# Sheet1.net
KiCad netlist of a schematic drawn in Altium Designer
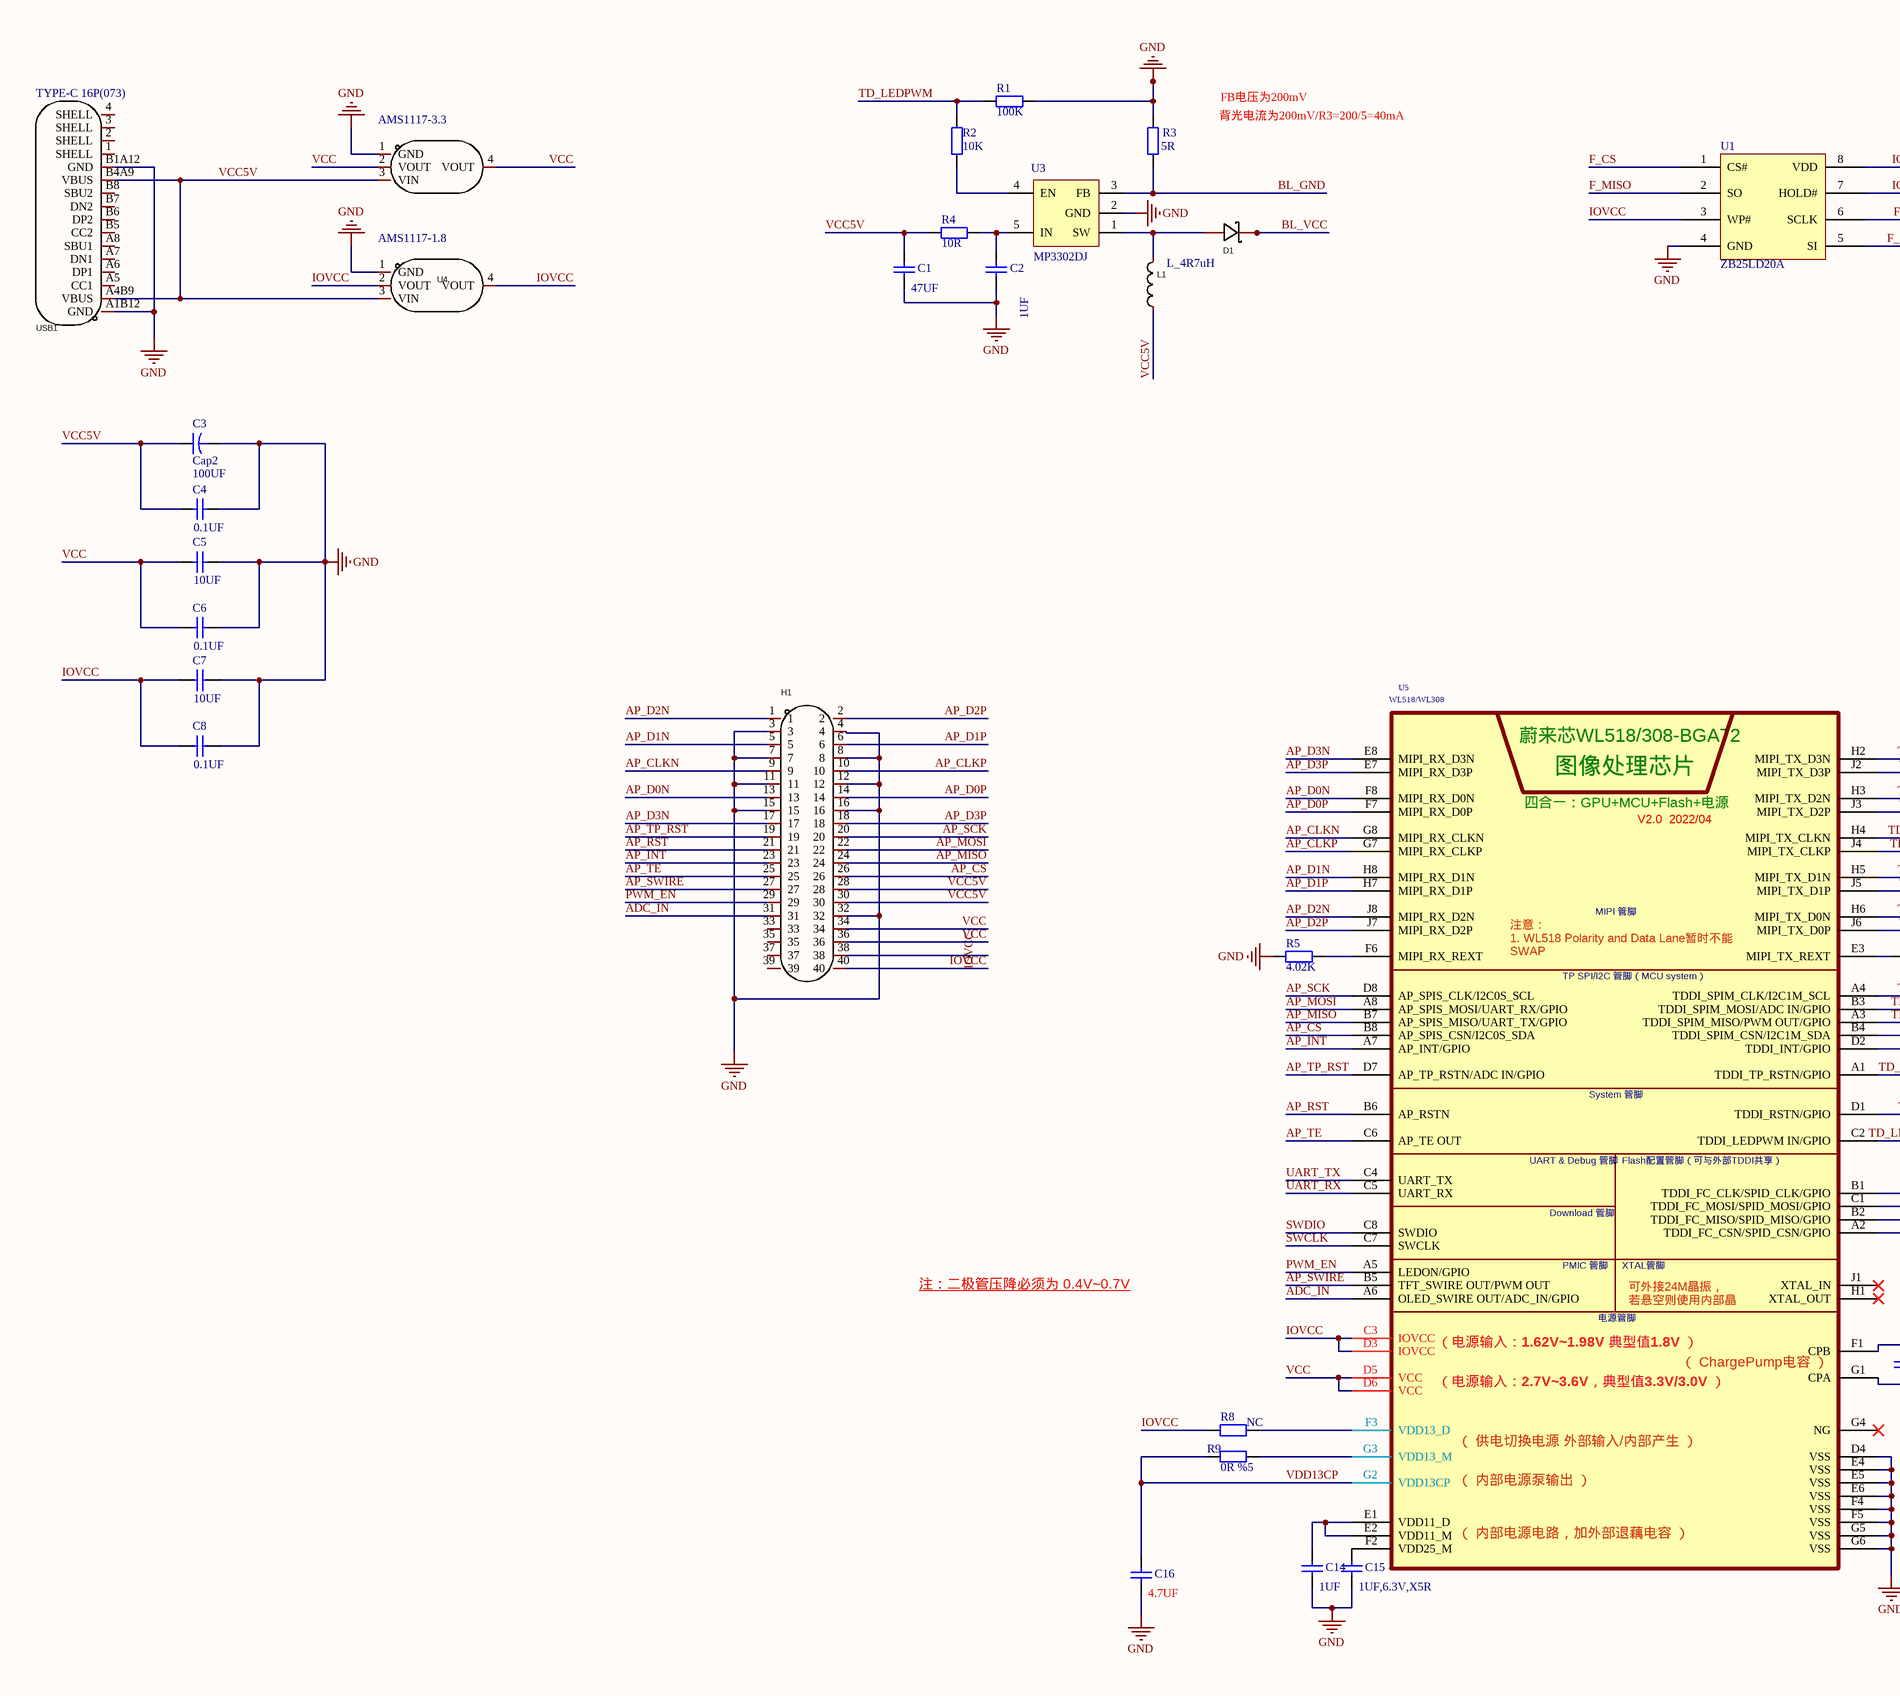
[diagram p0: Sheet1.SchDoc, left]
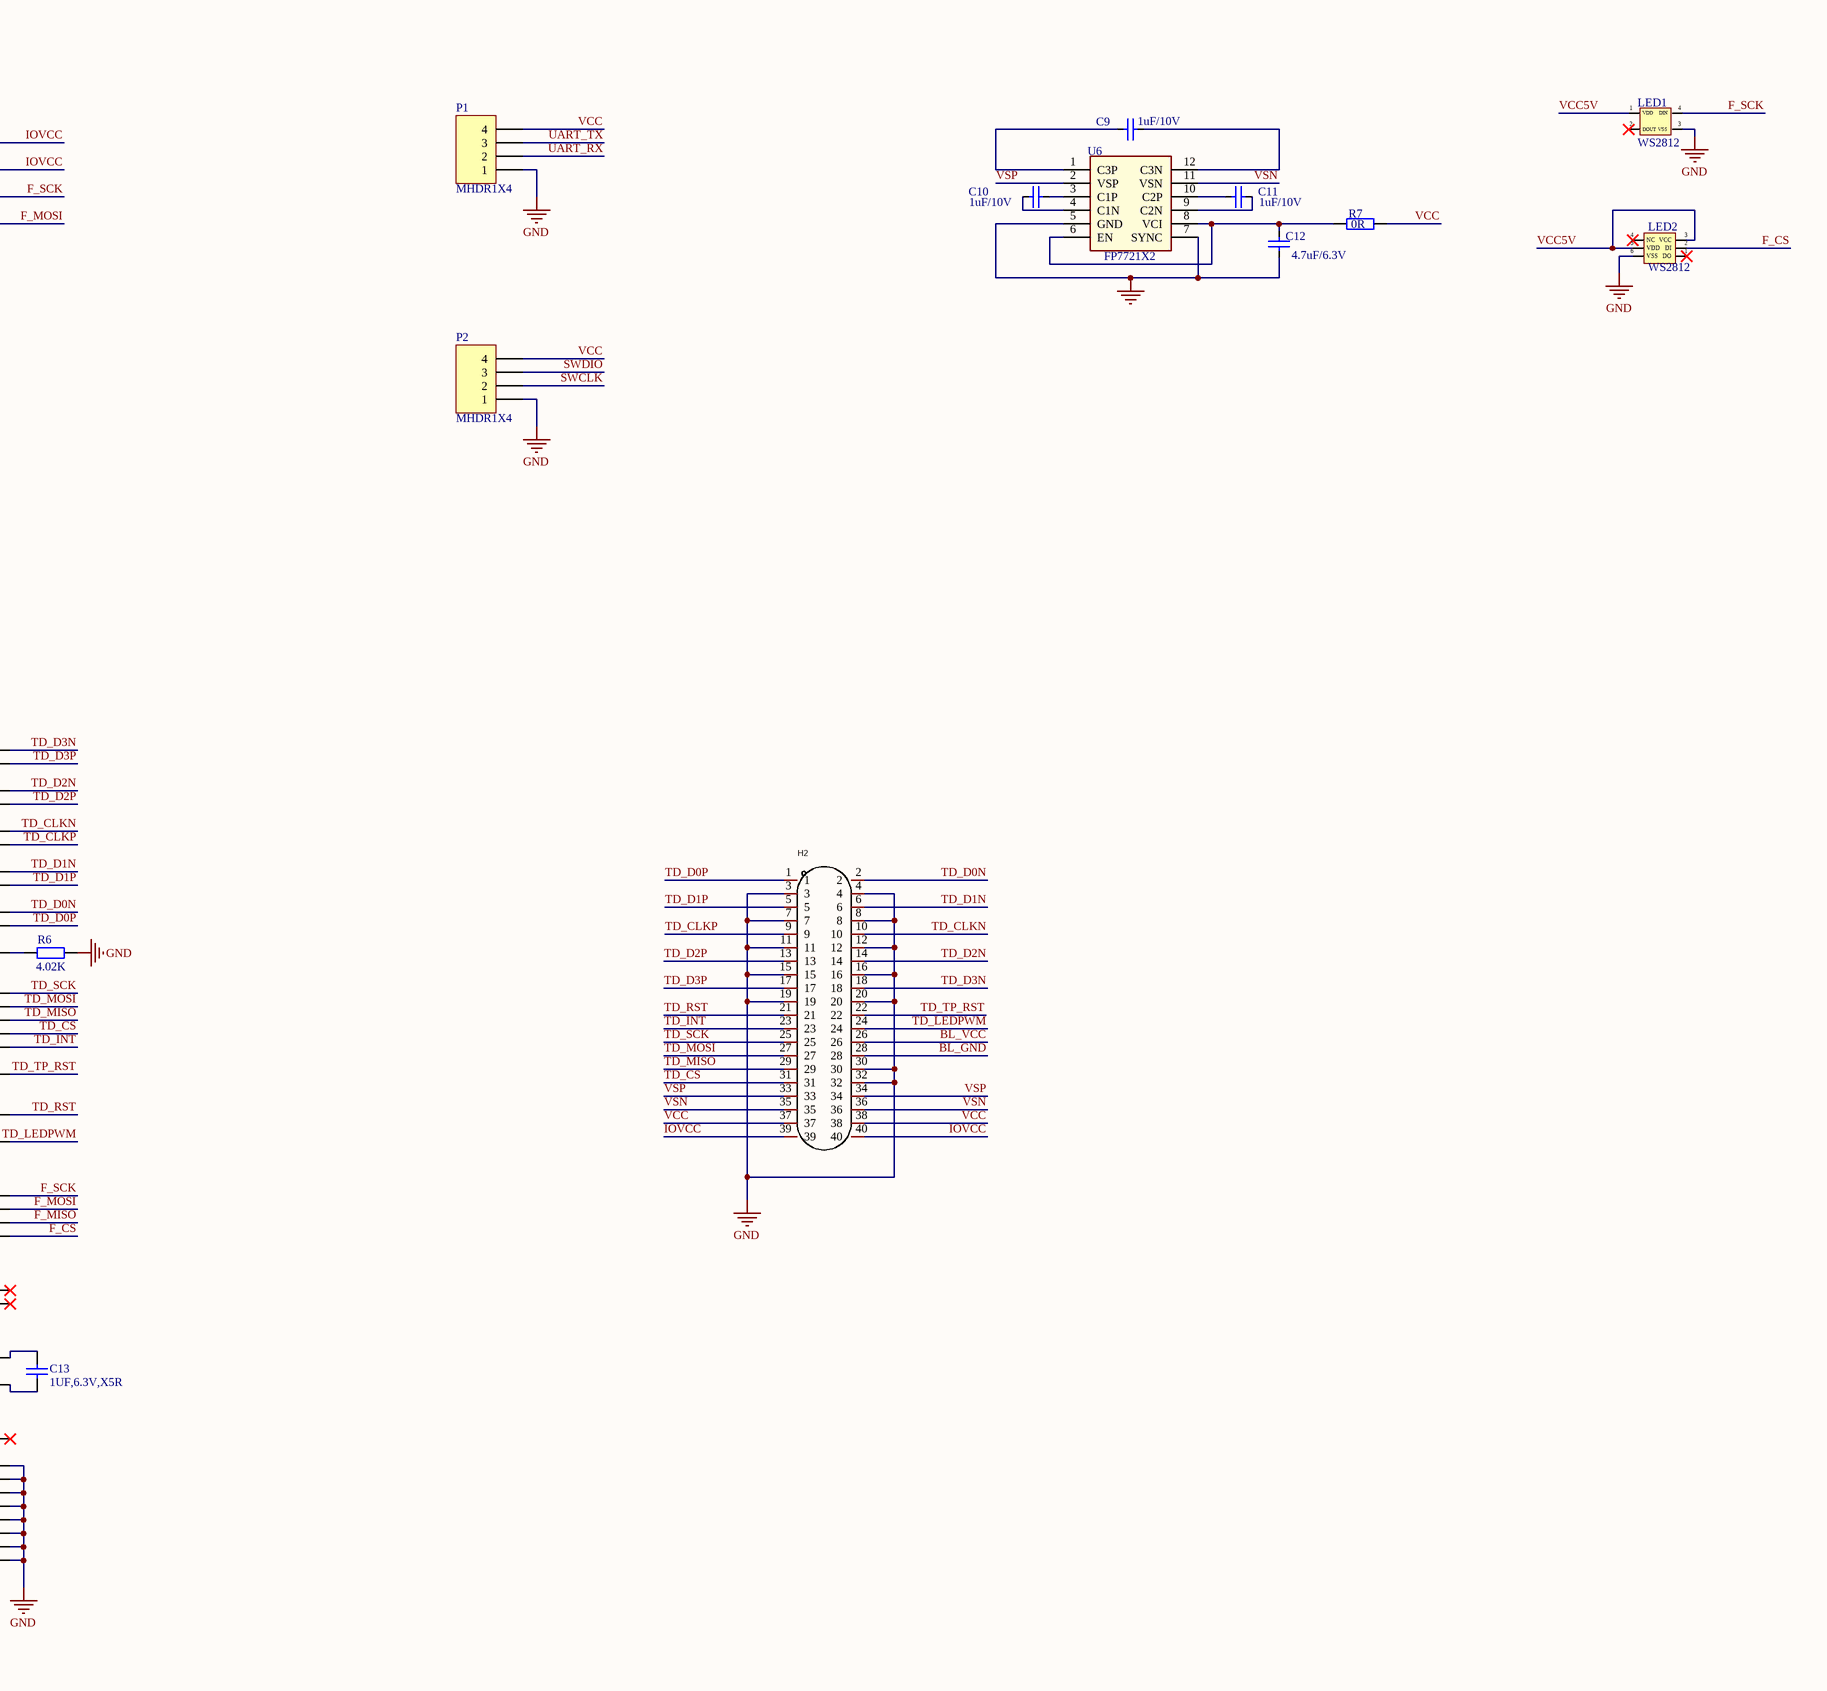
[diagram p1: Sheet1.SchDoc, right]

(export (version "E")
  (design (tool "Eeschema 10.0.6"))
  (components
    (comp (ref "C1")
      (value "47UF")
      (footprint "C0603")
      (description "Capacitor")
      (fields (field (name "PUBLISHER") "Altium Limited"))
      (libsource (lib "Miscellaneous Devices") (part "Cap"))
    )
    (comp (ref "C2")
      (value "1UF")
      (footprint "C0603")
      (description "Capacitor")
      (fields (field (name "PUBLISHER") "Altium Limited"))
      (libsource (lib "Miscellaneous Devices") (part "Cap"))
    )
    (comp (ref "C3")
      (value "Cap2")
      (footprint "CAPR5-4X5")
      (description "Capacitor")
      (fields (field (name "ALTIUM_VALUE") "100UF") (field (name "PUBLISHER") "Altium Limited"))
      (libsource (lib "Miscellaneous Devices") (part "Cap2"))
    )
    (comp (ref "C4")
      (value "0.1UF")
      (footprint "C0603")
      (description "Capacitor")
      (fields (field (name "PUBLISHER") "Altium Limited"))
      (libsource (lib "Miscellaneous Devices") (part "Cap"))
    )
    (comp (ref "C5")
      (value "10UF")
      (footprint "C0603")
      (description "Capacitor")
      (fields (field (name "PUBLISHER") "Altium Limited"))
      (libsource (lib "Miscellaneous Devices") (part "Cap"))
    )
    (comp (ref "C6")
      (value "0.1UF")
      (footprint "C0603")
      (description "Capacitor")
      (fields (field (name "PUBLISHER") "Altium Limited"))
      (libsource (lib "Miscellaneous Devices") (part "Cap"))
    )
    (comp (ref "C7")
      (value "10UF")
      (footprint "C0603")
      (description "Capacitor")
      (fields (field (name "PUBLISHER") "Altium Limited"))
      (libsource (lib "Miscellaneous Devices") (part "Cap"))
    )
    (comp (ref "C8")
      (value "0.1UF")
      (footprint "C0603")
      (description "Capacitor")
      (fields (field (name "PUBLISHER") "Altium Limited"))
      (libsource (lib "Miscellaneous Devices") (part "Cap"))
    )
    (comp (ref "C9")
      (value "1uF/10V")
      (footprint "C0603")
      (description "Capacitor")
      (libsource (lib "A51_SCH") (part "Cap"))
    )
    (comp (ref "C10")
      (value "1uF/10V")
      (footprint "C0603")
      (description "Capacitor")
      (libsource (lib "A51_SCH") (part "Cap"))
    )
    (comp (ref "C11")
      (value "1uF/10V")
      (footprint "C0603")
      (description "Capacitor")
      (libsource (lib "A51_SCH") (part "Cap"))
    )
    (comp (ref "C12")
      (value "4.7uF/6.3V")
      (footprint "C0603")
      (description "Capacitor")
      (libsource (lib "A51_SCH") (part "Cap"))
    )
    (comp (ref "C13")
      (value "1UF,6.3V,X5R")
      (footprint "C0603")
      (description "Capacitor")
      (fields (field (name "PUBLISHER") "Altium Limited"))
      (libsource (lib "Miscellaneous Devices") (part "Cap"))
    )
    (comp (ref "C14")
      (value "1UF")
      (footprint "C0603")
      (description "Capacitor")
      (fields (field (name "PUBLISHER") "Altium Limited"))
      (libsource (lib "Miscellaneous Devices") (part "Cap"))
    )
    (comp (ref "C15")
      (value "1UF,6.3V,X5R")
      (footprint "C0603")
      (description "Capacitor")
      (fields (field (name "PUBLISHER") "Altium Limited"))
      (libsource (lib "Miscellaneous Devices") (part "Cap"))
    )
    (comp (ref "C16")
      (value "4.7UF")
      (footprint "C0603")
      (description "Capacitor")
      (fields (field (name "PUBLISHER") "Altium Limited"))
      (libsource (lib "Miscellaneous Devices") (part "Cap"))
    )
    (comp (ref "D1")
      (value "1N5819HW-7-F")
      (footprint "SOD-123_L2.8-W1.8-LS3.7-FD")
      (fields (field (name "MANUFACTURER") "DIODES(美台)"))
      (libsource (lib "hu") (part "1N5819HW-7-F"))
    )
    (comp (ref "H1")
      (value "PZ200-2-20-Z")
      (footprint "HDR-TH_40P-P2.00-V-M-R2-C20-S2.00")
      (fields (field (name "MANUFACTURER") "HCTL(华灿天禄)"))
      (libsource (lib "hu") (part "排针2X20P"))
    )
    (comp (ref "H2")
      (value "PZ200-2-20-Z")
      (footprint "HDR-TH_40P-P2.00-V-M-R2-C20-S2.00")
      (fields (field (name "MANUFACTURER") "HCTL(华灿天禄)"))
      (libsource (lib "hu") (part "排针2X20P"))
    )
    (comp (ref "L1")
      (value "L_4R7uH")
      (footprint "IND-SMD_L5.2-W5.1")
      (description "4R7uH电感 SMD封装 SPM5030T-4R7M-HZ")
      (fields (field (name "MANUFACTURER") "TDK") (field (name "MANUFACTURER PART") "SPM5030T-4R7M-HZ"))
      (libsource (lib "hu") (part "SPM5030T-4R7M-HZ"))
    )
    (comp (ref "LED1")
      (value "WS2812")
      (footprint "WS2812_LED_4")
      (description "WS2812 LED 4P")
      (libsource (lib "hu") (part "WS2812_LED_4"))
    )
    (comp (ref "LED2")
      (value "WS2812")
      (footprint "WS2812_LED_6")
      (description "WS2812 LED 6P")
      (libsource (lib "hu") (part "WS2812_LED_6"))
    )
    (comp (ref "P1")
      (value "MHDR1X4")
      (footprint "MHDR1X4")
      (description "Header, 4-Pin")
      (fields (field (name "PUBLISHER") "Altium Limited"))
      (libsource (lib "Miscellaneous Connectors") (part "MHDR1X4"))
    )
    (comp (ref "P2")
      (value "MHDR1X4")
      (footprint "MHDR1X4")
      (description "Header, 4-Pin")
      (fields (field (name "PUBLISHER") "Altium Limited"))
      (libsource (lib "Miscellaneous Connectors") (part "MHDR1X4"))
    )
    (comp (ref "R1")
      (value "100K")
      (footprint "R0603")
      (description "Resistor")
      (fields (field (name "Comment") "Res2") (field (name "PUBLISHER") "Altium Limited"))
      (libsource (lib "Miscellaneous Devices") (part "Res2"))
    )
    (comp (ref "R2")
      (value "10K")
      (footprint "R0603")
      (description "Resistor")
      (fields (field (name "Comment") "Res2") (field (name "PUBLISHER") "Altium Limited"))
      (libsource (lib "") (part "Res2_2"))
    )
    (comp (ref "R3")
      (value "5R")
      (footprint "R0603")
      (description "Resistor")
      (fields (field (name "Comment") "Res2") (field (name "PUBLISHER") "Altium Limited"))
      (libsource (lib "") (part "Res2_3"))
    )
    (comp (ref "R4")
      (value "10R")
      (footprint "R0603")
      (description "Resistor")
      (fields (field (name "Comment") "Res2") (field (name "PUBLISHER") "Altium Limited"))
      (libsource (lib "Miscellaneous Devices") (part "Res2"))
    )
    (comp (ref "R5")
      (value "4.02K")
      (footprint "R0603")
      (description "Resistor")
      (fields (field (name "Comment") "Res2") (field (name "PUBLISHER") "Altium Limited"))
      (libsource (lib "Miscellaneous Devices") (part "Res2"))
    )
    (comp (ref "R6")
      (value "4.02K")
      (footprint "R0603")
      (description "Resistor")
      (fields (field (name "Comment") "Res2") (field (name "PUBLISHER") "Altium Limited"))
      (libsource (lib "") (part "Res2_1"))
    )
    (comp (ref "R7")
      (value "0R")
      (footprint "R0603")
      (description "Resistor")
      (libsource (lib "SCH") (part "Res_5%"))
    )
    (comp (ref "R8")
      (value "NC")
      (footprint "R0603")
      (description "Resistor")
      (fields (field (name "Comment") "Res2") (field (name "PUBLISHER") "Altium Limited"))
      (libsource (lib "Miscellaneous Devices") (part "Res2"))
    )
    (comp (ref "R9")
      (value "0R %5")
      (footprint "R0603")
      (description "Resistor")
      (fields (field (name "Comment") "Res2") (field (name "PUBLISHER") "Altium Limited"))
      (libsource (lib "Miscellaneous Devices") (part "Res2"))
    )
    (comp (ref "U1")
      (value "ZB25LD20A")
      (footprint "FLASH-WSON-8- 2X3mm")
      (description "FLASH")
      (libsource (lib "hu") (part "ZB25LD20A"))
    )
    (comp (ref "U2")
      (value "AMS1117-3.3")
      (footprint "SOT-223-3_L6.5-W3.4-P2.30-LS7.0-BR")
      (fields (field (name "MANUFACTURER") "美国AMS"))
      (libsource (lib "altium-import") (part "root_0_AMS1117-3.3_C6186_"))
    )
    (comp (ref "U3")
      (value "MP3302DJ")
      (footprint "TSOT-23-5_L2.9-W1.6-P0.95-LS2.8-BR")
      (description "5V-24V电平转换芯片")
      (libsource (lib "hu") (part "MP3302DJ"))
    )
    (comp (ref "U4")
      (value "AMS1117-1.8")
      (footprint "SOT-223-3_L6.5-W3.4-P2.30-LS7.0-BR")
      (fields (field (name "MANUFACTURER") "美国AMS") (field (name "MANUFACTURER PART") "AMS1117-3.3"))
      (libsource (lib "altium-import") (part "root_0_AMS1117-3.3_C6186_"))
    )
    (comp (ref "U5")
      (value "WL518/WL308")
      (footprint "WL518-BGA72 4.5mm*5mm")
      (libsource (lib "蔚来芯BGA72参考原理图库 v2.0-202204") (part "BGA72 4.5mm*5mm"))
    )
    (comp (ref "U6") (value "FP7721X2") (footprint "FP7721X2") (libsource (lib "A51_SCH") (part "FP7721X2")))
    (comp (ref "USB1")
      (value "TYPE-C 16P(073)")
      (footprint "USB-C-SMD_TYPE-C16PIN_C668624")
      (fields (field (name "MANUFACTURER") "SHOU HAN(首韩)"))
      (libsource (lib "altium-import") (part "root_2_TYPE-C 16P(073)_"))
    )
  )
  (nets
    (net (code "1") (name "/ADC_IN") (class "Default")
      (node (ref "H1") (pin "31") (pinfunction "31_31") (pintype "passive"))
      (node (ref "U5") (pin "A6") (pinfunction "OLED_SWIRE_OUT/ADC_IN/GPIO_A6") (pintype "passive"))
    )
    (net (code "2") (name "/AP_CLKN") (class "Default")
      (node (ref "H1") (pin "9") (pinfunction "9_9") (pintype "passive"))
      (node (ref "U5") (pin "G8") (pinfunction "MIPI_RX_CLKN_G8") (pintype "passive"))
    )
    (net (code "3") (name "/AP_CLKP") (class "Default")
      (node (ref "H1") (pin "10") (pinfunction "10_10") (pintype "passive"))
      (node (ref "U5") (pin "G7") (pinfunction "MIPI_RX_CLKP_G7") (pintype "passive"))
    )
    (net (code "4") (name "/AP_CS") (class "Default")
      (node (ref "H1") (pin "26") (pinfunction "26_26") (pintype "passive"))
      (node (ref "U5") (pin "B8") (pinfunction "AP_SPIS_CSN/I2C0S_SDA_B8") (pintype "passive"))
    )
    (net (code "5") (name "/AP_D0N") (class "Default")
      (node (ref "H1") (pin "13") (pinfunction "13_13") (pintype "passive"))
      (node (ref "U5") (pin "F8") (pinfunction "MIPI_RX_D0N_F8") (pintype "passive"))
    )
    (net (code "6") (name "/AP_D0P") (class "Default")
      (node (ref "H1") (pin "14") (pinfunction "14_14") (pintype "passive"))
      (node (ref "U5") (pin "F7") (pinfunction "MIPI_RX_D0P_F7") (pintype "passive"))
    )
    (net (code "7") (name "/AP_D1N") (class "Default")
      (node (ref "H1") (pin "5") (pinfunction "5_5") (pintype "passive"))
      (node (ref "U5") (pin "H8") (pinfunction "MIPI_RX_D1N_H8") (pintype "passive"))
    )
    (net (code "8") (name "/AP_D1P") (class "Default")
      (node (ref "H1") (pin "6") (pinfunction "6_6") (pintype "passive"))
      (node (ref "U5") (pin "H7") (pinfunction "MIPI_RX_D1P_H7") (pintype "passive"))
    )
    (net (code "9") (name "/AP_D2N") (class "Default")
      (node (ref "H1") (pin "1") (pinfunction "1_1") (pintype "passive"))
      (node (ref "U5") (pin "J8") (pinfunction "MIPI_RX_D2N_J8") (pintype "passive"))
    )
    (net (code "10") (name "/AP_D2P") (class "Default")
      (node (ref "H1") (pin "2") (pinfunction "2_2") (pintype "passive"))
      (node (ref "U5") (pin "J7") (pinfunction "MIPI_RX_D2P_J7") (pintype "passive"))
    )
    (net (code "11") (name "/AP_D3N") (class "Default")
      (node (ref "H1") (pin "17") (pinfunction "17_17") (pintype "passive"))
      (node (ref "U5") (pin "E8") (pinfunction "MIPI_RX_D3N_E8") (pintype "passive"))
    )
    (net (code "12") (name "/AP_D3P") (class "Default")
      (node (ref "H1") (pin "18") (pinfunction "18_18") (pintype "passive"))
      (node (ref "U5") (pin "E7") (pinfunction "MIPI_RX_D3P_E7") (pintype "passive"))
    )
    (net (code "13") (name "/AP_INT") (class "Default")
      (node (ref "H1") (pin "23") (pinfunction "23_23") (pintype "passive"))
      (node (ref "U5") (pin "A7") (pinfunction "AP_INT/GPIO_A7") (pintype "passive"))
    )
    (net (code "14") (name "/AP_MISO") (class "Default")
      (node (ref "H1") (pin "24") (pinfunction "24_24") (pintype "passive"))
      (node (ref "U5") (pin "B7") (pinfunction "AP_SPIS_MISO/UART_TX/GPIO_B7") (pintype "passive"))
    )
    (net (code "15") (name "/AP_MOSI") (class "Default")
      (node (ref "H1") (pin "22") (pinfunction "22_22") (pintype "passive"))
      (node (ref "U5") (pin "A8") (pinfunction "AP_SPIS_MOSI/UART_RX/GPIO_A8") (pintype "passive"))
    )
    (net (code "16") (name "/AP_RST") (class "Default")
      (node (ref "H1") (pin "21") (pinfunction "21_21") (pintype "passive"))
      (node (ref "U5") (pin "B6") (pinfunction "AP_RSTN_B6") (pintype "passive"))
    )
    (net (code "17") (name "/AP_SCK") (class "Default")
      (node (ref "H1") (pin "20") (pinfunction "20_20") (pintype "passive"))
      (node (ref "U5") (pin "D8") (pinfunction "AP_SPIS_CLK/I2C0S_SCL_D8") (pintype "passive"))
    )
    (net (code "18") (name "/AP_SWIRE") (class "Default")
      (node (ref "H1") (pin "27") (pinfunction "27_27") (pintype "passive"))
      (node (ref "U5") (pin "B5") (pinfunction "TFT_SWIRE_OUT/PWM_OUT_B5") (pintype "passive"))
    )
    (net (code "19") (name "/AP_TE") (class "Default")
      (node (ref "H1") (pin "25") (pinfunction "25_25") (pintype "passive"))
      (node (ref "U5") (pin "C6") (pinfunction "AP_TE_OUT_C6") (pintype "passive"))
    )
    (net (code "20") (name "/AP_TP_RST") (class "Default")
      (node (ref "H1") (pin "19") (pinfunction "19_19") (pintype "passive"))
      (node (ref "U5") (pin "D7") (pinfunction "AP_TP_RSTN/ADC_IN/GPIO_D7") (pintype "passive"))
    )
    (net (code "21") (name "/BL_GND") (class "Default")
      (node (ref "H2") (pin "28") (pinfunction "28_28") (pintype "passive"))
      (node (ref "R3") (pin "2") (pinfunction "2_2") (pintype "passive"))
      (node (ref "U3") (pin "3") (pinfunction "FB_3") (pintype "passive"))
    )
    (net (code "22") (name "/BL_VCC") (class "Default")
      (node (ref "D1") (pin "2") (pinfunction "K_2") (pintype "passive"))
      (node (ref "H2") (pin "26") (pinfunction "26_26") (pintype "passive"))
    )
    (net (code "23") (name "/F_CS") (class "Default")
      (node (ref "LED2") (pin "2") (pinfunction "DI_2") (pintype "passive"))
      (node (ref "U1") (pin "1") (pinfunction "CS#_1") (pintype "passive"))
      (node (ref "U5") (pin "A2") (pinfunction "TDDI_FC_CSN/SPID_CSN/GPIO_A2") (pintype "passive"))
    )
    (net (code "24") (name "/F_MISO") (class "Default")
      (node (ref "U1") (pin "2") (pinfunction "SO_2") (pintype "passive"))
      (node (ref "U5") (pin "B2") (pinfunction "TDDI_FC_MISO/SPID_MISO/GPIO_B2") (pintype "passive"))
    )
    (net (code "25") (name "/F_MOSI") (class "Default")
      (node (ref "U1") (pin "5") (pinfunction "SI_5") (pintype "passive"))
      (node (ref "U5") (pin "C1") (pinfunction "TDDI_FC_MOSI/SPID_MOSI/GPIO_C1") (pintype "passive"))
    )
    (net (code "26") (name "/F_SCK") (class "Default")
      (node (ref "LED1") (pin "4") (pinfunction "DIN_4") (pintype "passive"))
      (node (ref "U1") (pin "6") (pinfunction "SCLK_6") (pintype "passive"))
      (node (ref "U5") (pin "B1") (pinfunction "TDDI_FC_CLK/SPID_CLK/GPIO_B1") (pintype "passive"))
    )
    (net (code "27") (name "/IOVCC") (class "Default")
      (node (ref "C7") (pin "1") (pinfunction "1_1") (pintype "passive"))
      (node (ref "C8") (pin "1") (pinfunction "1_1") (pintype "passive"))
      (node (ref "H1") (pin "40") (pinfunction "40_40") (pintype "passive"))
      (node (ref "H2") (pin "39") (pinfunction "39_39") (pintype "passive"))
      (node (ref "H2") (pin "40") (pinfunction "40_40") (pintype "passive"))
      (node (ref "R8") (pin "2") (pinfunction "2_2") (pintype "passive"))
      (node (ref "U1") (pin "3") (pinfunction "WP#_3") (pintype "passive"))
      (node (ref "U1") (pin "7") (pinfunction "HOLD#_7") (pintype "passive"))
      (node (ref "U1") (pin "8") (pinfunction "VDD_8") (pintype "passive"))
      (node (ref "U4") (pin "2") (pinfunction "VOUT_2") (pintype "passive"))
      (node (ref "U4") (pin "4") (pinfunction "VOUT_4") (pintype "passive"))
      (node (ref "U5") (pin "C3") (pinfunction "IOVCC_C3") (pintype "passive"))
      (node (ref "U5") (pin "D3") (pinfunction "IOVCC_D3") (pintype "passive"))
    )
    (net (code "28") (name "/PWM_EN") (class "Default")
      (node (ref "H1") (pin "29") (pinfunction "29_29") (pintype "passive"))
      (node (ref "U5") (pin "A5") (pinfunction "LEDON/GPIO_A5") (pintype "passive"))
    )
    (net (code "29") (name "/SWCLK") (class "Default")
      (node (ref "P2") (pin "2") (pinfunction "2_2") (pintype "passive"))
      (node (ref "U5") (pin "C7") (pinfunction "SWCLK_C7") (pintype "passive"))
    )
    (net (code "30") (name "/SWDIO") (class "Default")
      (node (ref "P2") (pin "3") (pinfunction "3_3") (pintype "passive"))
      (node (ref "U5") (pin "C8") (pinfunction "SWDIO_C8") (pintype "passive"))
    )
    (net (code "31") (name "/TD_CLKN") (class "Default")
      (node (ref "H2") (pin "10") (pinfunction "10_10") (pintype "passive"))
      (node (ref "U5") (pin "H4") (pinfunction "MIPI_TX_CLKN_H4") (pintype "passive"))
    )
    (net (code "32") (name "/TD_CLKP") (class "Default")
      (node (ref "H2") (pin "9") (pinfunction "9_9") (pintype "passive"))
      (node (ref "U5") (pin "J4") (pinfunction "MIPI_TX_CLKP_J4") (pintype "passive"))
    )
    (net (code "33") (name "/TD_CS") (class "Default")
      (node (ref "H2") (pin "31") (pinfunction "31_31") (pintype "passive"))
      (node (ref "U5") (pin "B4") (pinfunction "TDDI_SPIM_CSN/I2C1M_SDA_B4") (pintype "passive"))
    )
    (net (code "34") (name "/TD_D0N") (class "Default")
      (node (ref "H2") (pin "2") (pinfunction "2_2") (pintype "passive"))
      (node (ref "U5") (pin "H6") (pinfunction "MIPI_TX_D0N_H6") (pintype "passive"))
    )
    (net (code "35") (name "/TD_D0P") (class "Default")
      (node (ref "H2") (pin "1") (pinfunction "1_1") (pintype "passive"))
      (node (ref "U5") (pin "J6") (pinfunction "MIPI_TX_D0P_J6") (pintype "passive"))
    )
    (net (code "36") (name "/TD_D1N") (class "Default")
      (node (ref "H2") (pin "6") (pinfunction "6_6") (pintype "passive"))
      (node (ref "U5") (pin "H5") (pinfunction "MIPI_TX_D1N_H5") (pintype "passive"))
    )
    (net (code "37") (name "/TD_D1P") (class "Default")
      (node (ref "H2") (pin "5") (pinfunction "5_5") (pintype "passive"))
      (node (ref "U5") (pin "J5") (pinfunction "MIPI_TX_D1P_J5") (pintype "passive"))
    )
    (net (code "38") (name "/TD_D2N") (class "Default")
      (node (ref "H2") (pin "14") (pinfunction "14_14") (pintype "passive"))
      (node (ref "U5") (pin "H3") (pinfunction "MIPI_TX_D2N_H3") (pintype "passive"))
    )
    (net (code "39") (name "/TD_D2P") (class "Default")
      (node (ref "H2") (pin "13") (pinfunction "13_13") (pintype "passive"))
      (node (ref "U5") (pin "J3") (pinfunction "MIPI_TX_D2P_J3") (pintype "passive"))
    )
    (net (code "40") (name "/TD_D3N") (class "Default")
      (node (ref "H2") (pin "18") (pinfunction "18_18") (pintype "passive"))
      (node (ref "U5") (pin "H2") (pinfunction "MIPI_TX_D3N_H2") (pintype "passive"))
    )
    (net (code "41") (name "/TD_D3P") (class "Default")
      (node (ref "H2") (pin "17") (pinfunction "17_17") (pintype "passive"))
      (node (ref "U5") (pin "J2") (pinfunction "MIPI_TX_D3P_J2") (pintype "passive"))
    )
    (net (code "42") (name "/TD_INT") (class "Default")
      (node (ref "H2") (pin "23") (pinfunction "23_23") (pintype "passive"))
      (node (ref "U5") (pin "D2") (pinfunction "TDDI_INT/GPIO_D2") (pintype "passive"))
    )
    (net (code "43") (name "/TD_LEDPWM") (class "Default")
      (node (ref "H2") (pin "24") (pinfunction "24_24") (pintype "passive"))
      (node (ref "R1") (pin "2") (pinfunction "2_2") (pintype "passive"))
      (node (ref "R2") (pin "2") (pinfunction "2_2") (pintype "passive"))
      (node (ref "U5") (pin "C2") (pinfunction "TDDI_LEDPWM_IN/GPIO_C2") (pintype "passive"))
    )
    (net (code "44") (name "/TD_MISO") (class "Default")
      (node (ref "H2") (pin "29") (pinfunction "29_29") (pintype "passive"))
      (node (ref "U5") (pin "A3") (pinfunction "TDDI_SPIM_MISO/PWM_OUT/GPIO_A3") (pintype "passive"))
    )
    (net (code "45") (name "/TD_MOSI") (class "Default")
      (node (ref "H2") (pin "27") (pinfunction "27_27") (pintype "passive"))
      (node (ref "U5") (pin "B3") (pinfunction "TDDI_SPIM_MOSI/ADC_IN/GPIO_B3") (pintype "passive"))
    )
    (net (code "46") (name "/TD_RST") (class "Default")
      (node (ref "H2") (pin "21") (pinfunction "21_21") (pintype "passive"))
      (node (ref "U5") (pin "D1") (pinfunction "TDDI_RSTN/GPIO_D1") (pintype "passive"))
    )
    (net (code "47") (name "/TD_SCK") (class "Default")
      (node (ref "H2") (pin "25") (pinfunction "25_25") (pintype "passive"))
      (node (ref "U5") (pin "A4") (pinfunction "TDDI_SPIM_CLK/I2C1M_SCL_A4") (pintype "passive"))
    )
    (net (code "48") (name "/TD_TP_RST") (class "Default")
      (node (ref "H2") (pin "22") (pinfunction "22_22") (pintype "passive"))
      (node (ref "U5") (pin "A1") (pinfunction "TDDI_TP_RSTN/GPIO_A1") (pintype "passive"))
    )
    (net (code "49") (name "/UART_RX") (class "Default")
      (node (ref "P1") (pin "2") (pinfunction "2_2") (pintype "passive"))
      (node (ref "U5") (pin "C5") (pinfunction "UART_RX_C5") (pintype "passive"))
    )
    (net (code "50") (name "/UART_TX") (class "Default")
      (node (ref "P1") (pin "3") (pinfunction "3_3") (pintype "passive"))
      (node (ref "U5") (pin "C4") (pinfunction "UART_TX_C4") (pintype "passive"))
    )
    (net (code "51") (name "/VCC") (class "Default")
      (node (ref "C5") (pin "1") (pinfunction "1_1") (pintype "passive"))
      (node (ref "C6") (pin "1") (pinfunction "1_1") (pintype "passive"))
      (node (ref "H1") (pin "34") (pinfunction "34_34") (pintype "passive"))
      (node (ref "H1") (pin "36") (pinfunction "36_36") (pintype "passive"))
      (node (ref "H2") (pin "37") (pinfunction "37_37") (pintype "passive"))
      (node (ref "H2") (pin "38") (pinfunction "38_38") (pintype "passive"))
      (node (ref "P1") (pin "4") (pinfunction "4_4") (pintype "passive"))
      (node (ref "P2") (pin "4") (pinfunction "4_4") (pintype "passive"))
      (node (ref "R7") (pin "2") (pinfunction "2_2") (pintype "passive"))
      (node (ref "U2") (pin "2") (pinfunction "VOUT_2") (pintype "passive"))
      (node (ref "U2") (pin "4") (pinfunction "VOUT_4") (pintype "passive"))
      (node (ref "U5") (pin "D5") (pinfunction "VCC_D5") (pintype "passive"))
      (node (ref "U5") (pin "D6") (pinfunction "VCC_D6") (pintype "passive"))
    )
    (net (code "52") (name "/VCC5V") (class "Default")
      (node (ref "C1") (pin "1") (pinfunction "1_1") (pintype "passive"))
      (node (ref "C3") (pin "1") (pinfunction "1_1") (pintype "passive"))
      (node (ref "C4") (pin "1") (pinfunction "1_1") (pintype "passive"))
      (node (ref "H1") (pin "28") (pinfunction "28_28") (pintype "passive"))
      (node (ref "H1") (pin "30") (pinfunction "30_30") (pintype "passive"))
      (node (ref "L1") (pin "1") (pinfunction "1_1") (pintype "passive"))
      (node (ref "LED1") (pin "1") (pinfunction "VDD_1") (pintype "passive"))
      (node (ref "LED2") (pin "3") (pinfunction "VCC_3") (pintype "passive"))
      (node (ref "LED2") (pin "5") (pinfunction "VDD_5") (pintype "passive"))
      (node (ref "R4") (pin "2") (pinfunction "2_2") (pintype "passive"))
      (node (ref "U2") (pin "3") (pinfunction "VIN_3") (pintype "passive"))
      (node (ref "U4") (pin "3") (pinfunction "VIN_3") (pintype "passive"))
      (node (ref "USB1") (pin "A4B9") (pinfunction "VBUS_A4B9") (pintype "passive"))
      (node (ref "USB1") (pin "B4A9") (pinfunction "VBUS_B4A9") (pintype "passive"))
    )
    (net (code "53") (name "/VDD13CP") (class "Default")
      (node (ref "C16") (pin "1") (pinfunction "1_1") (pintype "passive"))
      (node (ref "R9") (pin "2") (pinfunction "2_2") (pintype "passive"))
      (node (ref "U5") (pin "G2") (pinfunction "VDD13CP_G2") (pintype "passive"))
    )
    (net (code "54") (name "/VSN") (class "Default")
      (node (ref "H2") (pin "35") (pinfunction "35_35") (pintype "passive"))
      (node (ref "H2") (pin "36") (pinfunction "36_36") (pintype "passive"))
      (node (ref "U6") (pin "11") (pinfunction "VSN_11") (pintype "passive"))
    )
    (net (code "55") (name "/VSP") (class "Default")
      (node (ref "H2") (pin "33") (pinfunction "33_33") (pintype "passive"))
      (node (ref "H2") (pin "34") (pinfunction "34_34") (pintype "passive"))
      (node (ref "U6") (pin "2") (pinfunction "VSP_2") (pintype "passive"))
    )
    (net (code "56") (name "GND") (class "Default")
      (node (ref "C1") (pin "2") (pinfunction "2_2") (pintype "passive"))
      (node (ref "C12") (pin "2") (pinfunction "2_2") (pintype "passive"))
      (node (ref "C14") (pin "2") (pinfunction "2_2") (pintype "passive"))
      (node (ref "C15") (pin "2") (pinfunction "2_2") (pintype "passive"))
      (node (ref "C16") (pin "2") (pinfunction "2_2") (pintype "passive"))
      (node (ref "C2") (pin "2") (pinfunction "2_2") (pintype "passive"))
      (node (ref "C3") (pin "2") (pinfunction "2_2") (pintype "passive"))
      (node (ref "C4") (pin "2") (pinfunction "2_2") (pintype "passive"))
      (node (ref "C5") (pin "2") (pinfunction "2_2") (pintype "passive"))
      (node (ref "C6") (pin "2") (pinfunction "2_2") (pintype "passive"))
      (node (ref "C7") (pin "2") (pinfunction "2_2") (pintype "passive"))
      (node (ref "C8") (pin "2") (pinfunction "2_2") (pintype "passive"))
      (node (ref "H1") (pin "11") (pinfunction "11_11") (pintype "passive"))
      (node (ref "H1") (pin "12") (pinfunction "12_12") (pintype "passive"))
      (node (ref "H1") (pin "15") (pinfunction "15_15") (pintype "passive"))
      (node (ref "H1") (pin "16") (pinfunction "16_16") (pintype "passive"))
      (node (ref "H1") (pin "3") (pinfunction "3_3") (pintype "passive"))
      (node (ref "H1") (pin "32") (pinfunction "32_32") (pintype "passive"))
      (node (ref "H1") (pin "4") (pinfunction "4_4") (pintype "passive"))
      (node (ref "H1") (pin "7") (pinfunction "7_7") (pintype "passive"))
      (node (ref "H1") (pin "8") (pinfunction "8_8") (pintype "passive"))
      (node (ref "H2") (pin "11") (pinfunction "11_11") (pintype "passive"))
      (node (ref "H2") (pin "12") (pinfunction "12_12") (pintype "passive"))
      (node (ref "H2") (pin "15") (pinfunction "15_15") (pintype "passive"))
      (node (ref "H2") (pin "16") (pinfunction "16_16") (pintype "passive"))
      (node (ref "H2") (pin "19") (pinfunction "19_19") (pintype "passive"))
      (node (ref "H2") (pin "20") (pinfunction "20_20") (pintype "passive"))
      (node (ref "H2") (pin "3") (pinfunction "3_3") (pintype "passive"))
      (node (ref "H2") (pin "30") (pinfunction "30_30") (pintype "passive"))
      (node (ref "H2") (pin "32") (pinfunction "32_32") (pintype "passive"))
      (node (ref "H2") (pin "4") (pinfunction "4_4") (pintype "passive"))
      (node (ref "H2") (pin "7") (pinfunction "7_7") (pintype "passive"))
      (node (ref "H2") (pin "8") (pinfunction "8_8") (pintype "passive"))
      (node (ref "LED1") (pin "3") (pinfunction "VSS_3") (pintype "passive"))
      (node (ref "LED2") (pin "6") (pinfunction "VSS_6") (pintype "passive"))
      (node (ref "P1") (pin "1") (pinfunction "1_1") (pintype "passive"))
      (node (ref "P2") (pin "1") (pinfunction "1_1") (pintype "passive"))
      (node (ref "R1") (pin "1") (pinfunction "1_1") (pintype "passive"))
      (node (ref "R3") (pin "1") (pinfunction "1_1") (pintype "passive"))
      (node (ref "R5") (pin "2") (pinfunction "2_2") (pintype "passive"))
      (node (ref "R6") (pin "2") (pinfunction "2_2") (pintype "passive"))
      (node (ref "U1") (pin "4") (pinfunction "GND_4") (pintype "passive"))
      (node (ref "U2") (pin "1") (pinfunction "GND_1") (pintype "passive"))
      (node (ref "U3") (pin "2") (pinfunction "GND_2") (pintype "passive"))
      (node (ref "U4") (pin "1") (pinfunction "GND_1") (pintype "passive"))
      (node (ref "U5") (pin "D4") (pinfunction "VSS_D4") (pintype "passive"))
      (node (ref "U5") (pin "E4") (pinfunction "VSS_E4") (pintype "passive"))
      (node (ref "U5") (pin "E5") (pinfunction "VSS_E5") (pintype "passive"))
      (node (ref "U5") (pin "E6") (pinfunction "VSS_E6") (pintype "passive"))
      (node (ref "U5") (pin "F4") (pinfunction "VSS_F4") (pintype "passive"))
      (node (ref "U5") (pin "F5") (pinfunction "VSS_F5") (pintype "passive"))
      (node (ref "U5") (pin "G5") (pinfunction "VSS_G5") (pintype "passive"))
      (node (ref "U5") (pin "G6") (pinfunction "VSS_G6") (pintype "passive"))
      (node (ref "U6") (pin "5") (pinfunction "GND_5") (pintype "passive"))
      (node (ref "U6") (pin "7") (pinfunction "SYNC_7") (pintype "passive"))
      (node (ref "USB1") (pin "A1B12") (pinfunction "GND_A1B12") (pintype "passive"))
      (node (ref "USB1") (pin "B1A12") (pinfunction "GND_B1A12") (pintype "passive"))
    )
    (net (code "57") (name "Net-(D1-A)") (class "Default")
      (node (ref "D1") (pin "1") (pinfunction "A_1") (pintype "passive"))
      (node (ref "L1") (pin "2") (pinfunction "2_2") (pintype "passive"))
      (node (ref "U3") (pin "1") (pinfunction "SW_1") (pintype "passive"))
    )
    (net (code "58") (name "Net-(U3-EN)") (class "Default")
      (node (ref "R2") (pin "1") (pinfunction "1_1") (pintype "passive"))
      (node (ref "U3") (pin "4") (pinfunction "EN_4") (pintype "passive"))
    )
    (net (code "59") (name "Net-(U3-IN)") (class "Default")
      (node (ref "C2") (pin "1") (pinfunction "1_1") (pintype "passive"))
      (node (ref "R4") (pin "1") (pinfunction "1_1") (pintype "passive"))
      (node (ref "U3") (pin "5") (pinfunction "IN_5") (pintype "passive"))
    )
    (net (code "60") (name "Net-(U5-CPA)") (class "Default")
      (node (ref "C13") (pin "1") (pinfunction "1_1") (pintype "passive"))
      (node (ref "U5") (pin "G1") (pinfunction "CPA_G1") (pintype "passive"))
    )
    (net (code "61") (name "Net-(U5-CPB)") (class "Default")
      (node (ref "C13") (pin "2") (pinfunction "2_2") (pintype "passive"))
      (node (ref "U5") (pin "F1") (pinfunction "CPB_F1") (pintype "passive"))
    )
    (net (code "62") (name "Net-(U5-MIPI_RX_REXT)") (class "Default")
      (node (ref "R5") (pin "1") (pinfunction "1_1") (pintype "passive"))
      (node (ref "U5") (pin "F6") (pinfunction "MIPI_RX_REXT_F6") (pintype "passive"))
    )
    (net (code "63") (name "Net-(U5-MIPI_TX_REXT)") (class "Default")
      (node (ref "R6") (pin "1") (pinfunction "1_1") (pintype "passive"))
      (node (ref "U5") (pin "E3") (pinfunction "MIPI_TX_REXT_E3") (pintype "passive"))
    )
    (net (code "64") (name "Net-(U5-VDD11_D)") (class "Default")
      (node (ref "C14") (pin "1") (pinfunction "1_1") (pintype "passive"))
      (node (ref "U5") (pin "E1") (pinfunction "VDD11_D_E1") (pintype "passive"))
      (node (ref "U5") (pin "E2") (pinfunction "VDD11_M_E2") (pintype "passive"))
    )
    (net (code "65") (name "Net-(U5-VDD13_D)") (class "Default")
      (node (ref "R8") (pin "1") (pinfunction "1_1") (pintype "passive"))
      (node (ref "U5") (pin "F3") (pinfunction "VDD13_D_F3") (pintype "passive"))
    )
    (net (code "66") (name "Net-(U5-VDD13_M)") (class "Default")
      (node (ref "R9") (pin "1") (pinfunction "1_1") (pintype "passive"))
      (node (ref "U5") (pin "G3") (pinfunction "VDD13_M_G3") (pintype "passive"))
    )
    (net (code "67") (name "Net-(U5-VDD25_M)") (class "Default")
      (node (ref "C15") (pin "1") (pinfunction "1_1") (pintype "passive"))
      (node (ref "U5") (pin "F2") (pinfunction "VDD25_M_F2") (pintype "passive"))
    )
    (net (code "68") (name "Net-(U6-C1N)") (class "Default")
      (node (ref "C10") (pin "2") (pinfunction "2_2") (pintype "passive"))
      (node (ref "U6") (pin "4") (pinfunction "C1N_4") (pintype "passive"))
    )
    (net (code "69") (name "Net-(U6-C1P)") (class "Default")
      (node (ref "C10") (pin "1") (pinfunction "1_1") (pintype "passive"))
      (node (ref "U6") (pin "3") (pinfunction "C1P_3") (pintype "passive"))
    )
    (net (code "70") (name "Net-(U6-C2N)") (class "Default")
      (node (ref "C11") (pin "1") (pinfunction "1_1") (pintype "passive"))
      (node (ref "U6") (pin "9") (pinfunction "C2N_9") (pintype "passive"))
    )
    (net (code "71") (name "Net-(U6-C2P)") (class "Default")
      (node (ref "C11") (pin "2") (pinfunction "2_2") (pintype "passive"))
      (node (ref "U6") (pin "10") (pinfunction "C2P_10") (pintype "passive"))
    )
    (net (code "72") (name "Net-(U6-C3N)") (class "Default")
      (node (ref "C9") (pin "1") (pinfunction "1_1") (pintype "passive"))
      (node (ref "U6") (pin "12") (pinfunction "C3N_12") (pintype "passive"))
    )
    (net (code "73") (name "Net-(U6-C3P)") (class "Default")
      (node (ref "C9") (pin "2") (pinfunction "2_2") (pintype "passive"))
      (node (ref "U6") (pin "1") (pinfunction "C3P_1") (pintype "passive"))
    )
    (net (code "74") (name "Net-(U6-EN)") (class "Default")
      (node (ref "C12") (pin "1") (pinfunction "1_1") (pintype "passive"))
      (node (ref "R7") (pin "1") (pinfunction "1_1") (pintype "passive"))
      (node (ref "U6") (pin "6") (pinfunction "EN_6") (pintype "passive"))
      (node (ref "U6") (pin "8") (pinfunction "VCI_8") (pintype "passive"))
    )
    (net (code "75") (name "unconnected-(H1-Pad33)") (class "Default")
      (node (ref "H1") (pin "33") (pinfunction "33_33") (pintype "passive"))
    )
    (net (code "76") (name "unconnected-(H1-Pad35)") (class "Default")
      (node (ref "H1") (pin "35") (pinfunction "35_35") (pintype "passive"))
    )
    (net (code "77") (name "unconnected-(H1-Pad37)") (class "Default")
      (node (ref "H1") (pin "37") (pinfunction "37_37") (pintype "passive"))
    )
    (net (code "78") (name "unconnected-(H1-Pad38)") (class "Default")
      (node (ref "H1") (pin "38") (pinfunction "38_38") (pintype "passive"))
    )
    (net (code "79") (name "unconnected-(H1-Pad39)") (class "Default")
      (node (ref "H1") (pin "39") (pinfunction "39_39") (pintype "passive"))
    )
    (net (code "80") (name "unconnected-(LED1-DOUT-Pad2)") (class "Default")
      (node (ref "LED1") (pin "2") (pinfunction "DOUT_2") (pintype "passive+no_connect"))
    )
    (net (code "81") (name "unconnected-(LED2-DO-Pad1)") (class "Default")
      (node (ref "LED2") (pin "1") (pinfunction "DO_1") (pintype "passive+no_connect"))
    )
    (net (code "82") (name "unconnected-(LED2-NC-Pad4)") (class "Default")
      (node (ref "LED2") (pin "4") (pinfunction "NC_4") (pintype "passive+no_connect"))
    )
    (net (code "83") (name "unconnected-(U5-NG-PadG4)") (class "Default")
      (node (ref "U5") (pin "G4") (pinfunction "NG_G4") (pintype "passive+no_connect"))
    )
    (net (code "84") (name "unconnected-(U5-XTAL_IN-PadJ1)") (class "Default")
      (node (ref "U5") (pin "J1") (pinfunction "XTAL_IN_J1") (pintype "passive+no_connect"))
    )
    (net (code "85") (name "unconnected-(U5-XTAL_OUT-PadH1)") (class "Default")
      (node (ref "U5") (pin "H1") (pinfunction "XTAL_OUT_H1") (pintype "passive+no_connect"))
    )
    (net (code "86") (name "unconnected-(USB1-CC1-PadA5)") (class "Default")
      (node (ref "USB1") (pin "A5") (pinfunction "CC1_A5") (pintype "passive"))
    )
    (net (code "87") (name "unconnected-(USB1-CC2-PadB5)") (class "Default")
      (node (ref "USB1") (pin "B5") (pinfunction "CC2_B5") (pintype "passive"))
    )
    (net (code "88") (name "unconnected-(USB1-DN1-PadA7)") (class "Default")
      (node (ref "USB1") (pin "A7") (pinfunction "DN1_A7") (pintype "passive"))
    )
    (net (code "89") (name "unconnected-(USB1-DN2-PadB7)") (class "Default")
      (node (ref "USB1") (pin "B7") (pinfunction "DN2_B7") (pintype "passive"))
    )
    (net (code "90") (name "unconnected-(USB1-DP1-PadA6)") (class "Default")
      (node (ref "USB1") (pin "A6") (pinfunction "DP1_A6") (pintype "passive"))
    )
    (net (code "91") (name "unconnected-(USB1-DP2-PadB6)") (class "Default")
      (node (ref "USB1") (pin "B6") (pinfunction "DP2_B6") (pintype "passive"))
    )
    (net (code "92") (name "unconnected-(USB1-SBU1-PadA8)") (class "Default")
      (node (ref "USB1") (pin "A8") (pinfunction "SBU1_A8") (pintype "passive"))
    )
    (net (code "93") (name "unconnected-(USB1-SBU2-PadB8)") (class "Default")
      (node (ref "USB1") (pin "B8") (pinfunction "SBU2_B8") (pintype "passive"))
    )
    (net (code "94") (name "unconnected-(USB1-SHELL-Pad1)") (class "Default")
      (node (ref "USB1") (pin "1") (pinfunction "SHELL_1") (pintype "passive"))
    )
    (net (code "95") (name "unconnected-(USB1-SHELL-Pad2)") (class "Default")
      (node (ref "USB1") (pin "2") (pinfunction "SHELL_2") (pintype "passive"))
    )
    (net (code "96") (name "unconnected-(USB1-SHELL-Pad3)") (class "Default")
      (node (ref "USB1") (pin "3") (pinfunction "SHELL_3") (pintype "passive"))
    )
    (net (code "97") (name "unconnected-(USB1-SHELL-Pad4)") (class "Default")
      (node (ref "USB1") (pin "4") (pinfunction "SHELL_4") (pintype "passive"))
    )
  )
)
